# Connectors.net
KiCad netlist of a schematic drawn in Altium Designer
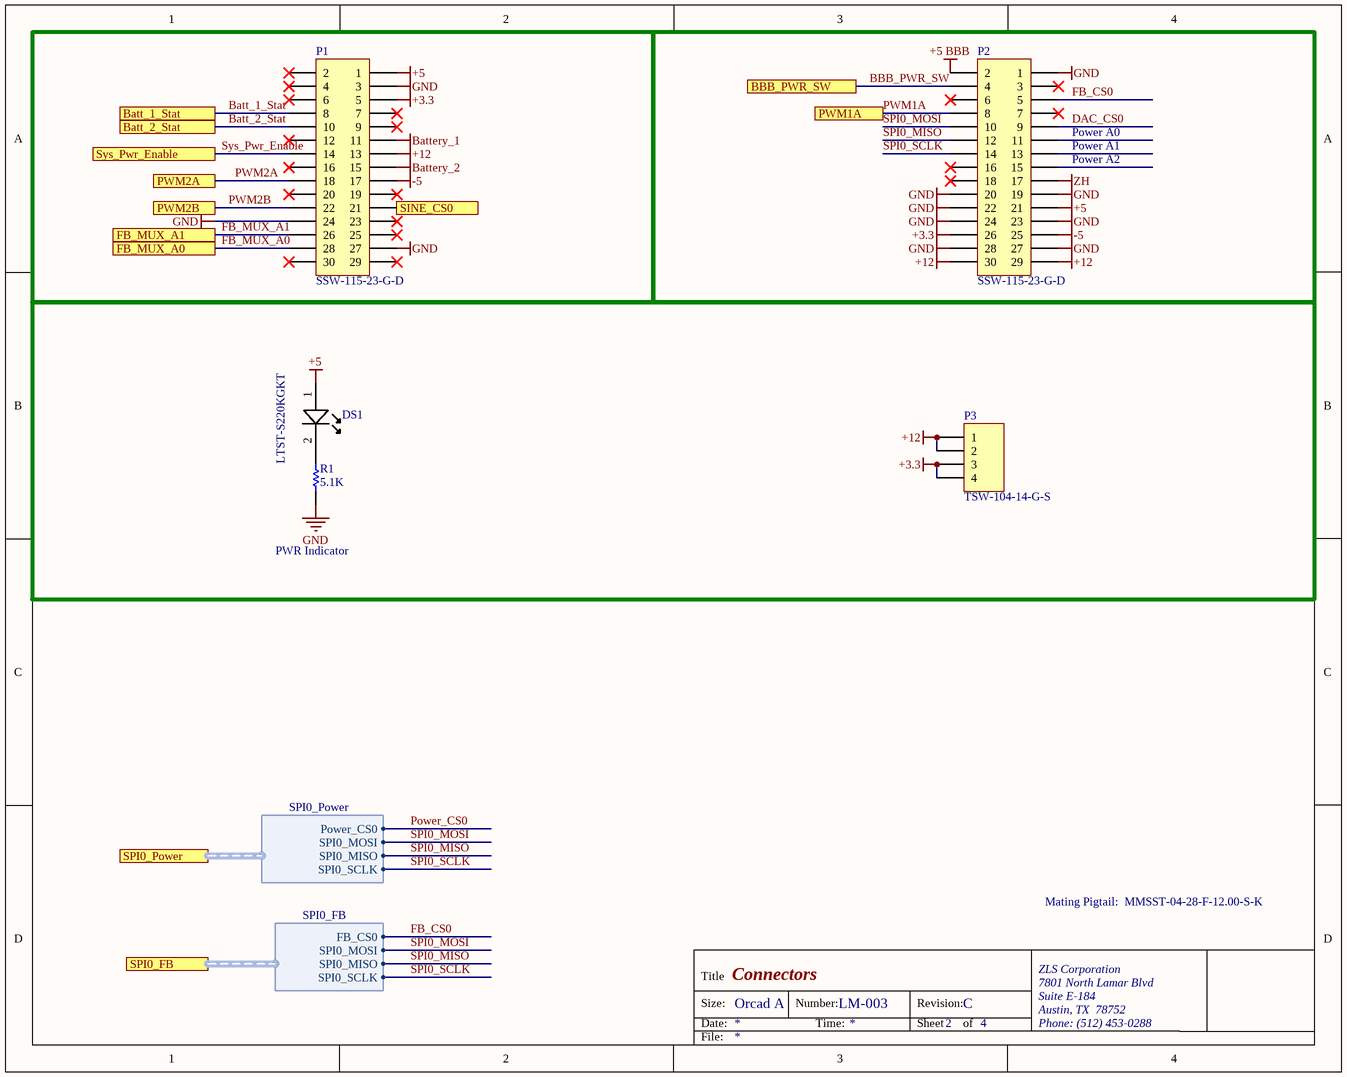
[diagram p0: Connectors.SchDoc]

(export (version "E")
  (design (tool "Eeschema 10.0.6"))
  (components
    (comp (ref "DS1")
      (value "Lite-On LTST-S220KGKT Green LED, 571 nm 2012 (0805) Side View, Rectangle Lens SMD package")
      (footprint "0805C_L")
      (fields
        (field (name "MANUFACTURER") "Vishay / Lite-On")
        (field (name "MANUFACTURER PART NUMBER") "LTST-S220KGKT")
      )
      (libsource (lib "*") (part "LED A/K"))
    )
    (comp (ref "P1")
      (value "SSW-115-23-G-D")
      (footprint "SSW-115-23-G-D")
      (description "Header, 15-Pin, Dual row")
      (fields (field (name "MANUFACTURER") "Samtec Inc."))
      (libsource (lib "Miscellaneous Connectors") (part "Header 15X2"))
    )
    (comp (ref "P2")
      (value "SSW-115-23-G-D")
      (footprint "SSW-115-23-G-D")
      (description "Header, 15-Pin, Dual row")
      (fields (field (name "MANUFACTURER") "Samtec Inc."))
      (libsource (lib "Miscellaneous Connectors") (part "Header 15X2"))
    )
    (comp (ref "P3")
      (value "TSW-104-14-G-S")
      (footprint "HDR1X4")
      (description "Header, 4-Pin")
      (fields (field (name "MANUFACTURER") "Samtec Inc."))
      (libsource (lib "Miscellaneous Connectors") (part "Header 4"))
    )
    (comp (ref "R1")
      (value "5.1K")
      (footprint "RESC0805(2012)_L")
      (description "RES SMD 5.1K OHM 5% 1/8W 0805")
      (fields
        (field (name "MANUFACTURER") "Vishay Dale")
        (field (name "MANUFACTURER PART NUMBER") "CRCW08055K10JNEA")
      )
      (libsource (lib "Altium Content Vault") (part "CMP-1013-00215-1"))
    )
  )
  (nets
    (net (code "3") (name "+3.3") (class "Default")
      (node (ref "P1") (pin "5") (pinfunction "5_5") (pintype "passive"))
      (node (ref "P2") (pin "26") (pinfunction "26_26") (pintype "passive"))
      (node (ref "P3") (pin "3") (pinfunction "3_3") (pintype "passive"))
      (node (ref "P3") (pin "4") (pinfunction "4_4") (pintype "passive"))
    )
    (net (code "4") (name "+5") (class "Default")
      (node (ref "DS1") (pin "1") (pinfunction "A_1") (pintype "passive"))
      (node (ref "P1") (pin "1") (pinfunction "1_1") (pintype "passive"))
      (node (ref "P2") (pin "21") (pinfunction "21_21") (pintype "passive"))
    )
    (net (code "5") (name "+5 BBB") (class "Default")
      (node (ref "P2") (pin "2") (pinfunction "2_2") (pintype "passive"))
    )
    (net (code "6") (name "+12") (class "Default")
      (node (ref "P1") (pin "13") (pinfunction "13_13") (pintype "passive"))
      (node (ref "P2") (pin "29") (pinfunction "29_29") (pintype "passive"))
      (node (ref "P2") (pin "30") (pinfunction "30_30") (pintype "passive"))
      (node (ref "P3") (pin "1") (pinfunction "1_1") (pintype "passive"))
      (node (ref "P3") (pin "2") (pinfunction "2_2") (pintype "passive"))
    )
    (net (code "7") (name "-5") (class "Default")
      (node (ref "P1") (pin "17") (pinfunction "17_17") (pintype "passive"))
      (node (ref "P2") (pin "25") (pinfunction "25_25") (pintype "passive"))
    )
    (net (code "8") (name "/BBB_PWR_SW") (class "Default")
      (node (ref "P2") (pin "4") (pinfunction "4_4") (pintype "passive"))
    )
    (net (code "9") (name "/Batt_1_Stat") (class "Default")
      (node (ref "P1") (pin "8") (pinfunction "8_8") (pintype "passive"))
    )
    (net (code "10") (name "/Batt_2_Stat") (class "Default")
      (node (ref "P1") (pin "10") (pinfunction "10_10") (pintype "passive"))
    )
    (net (code "11") (name "/DAC_CS0") (class "Default")
      (node (ref "P2") (pin "9") (pinfunction "9_9") (pintype "passive"))
    )
    (net (code "12") (name "/FB_CS0") (class "Default")
      (node (ref "P2") (pin "5") (pinfunction "5_5") (pintype "passive"))
    )
    (net (code "13") (name "/FB_MUX_A0") (class "Default")
      (node (ref "P1") (pin "28") (pinfunction "28_28") (pintype "passive"))
    )
    (net (code "14") (name "/FB_MUX_A1") (class "Default")
      (node (ref "P1") (pin "26") (pinfunction "26_26") (pintype "passive"))
    )
    (net (code "15") (name "/PWM1A") (class "Default")
      (node (ref "P2") (pin "8") (pinfunction "8_8") (pintype "passive"))
    )
    (net (code "16") (name "/PWM2A") (class "Default")
      (node (ref "P1") (pin "18") (pinfunction "18_18") (pintype "passive"))
    )
    (net (code "17") (name "/PWM2B") (class "Default")
      (node (ref "P1") (pin "22") (pinfunction "22_22") (pintype "passive"))
    )
    (net (code "19") (name "/SINE_CS0") (class "Default")
      (node (ref "P1") (pin "21") (pinfunction "21_21") (pintype "passive"))
    )
    (net (code "20") (name "/SPI0_MISO") (class "Default")
      (node (ref "P2") (pin "12") (pinfunction "12_12") (pintype "passive"))
    )
    (net (code "21") (name "/SPI0_MOSI") (class "Default")
      (node (ref "P2") (pin "10") (pinfunction "10_10") (pintype "passive"))
    )
    (net (code "22") (name "/SPI0_SCLK") (class "Default")
      (node (ref "P2") (pin "14") (pinfunction "14_14") (pintype "passive"))
    )
    (net (code "23") (name "/Sys_Pwr_Enable") (class "Default")
      (node (ref "P1") (pin "14") (pinfunction "14_14") (pintype "passive"))
    )
    (net (code "26") (name "Battery_1") (class "Default")
      (node (ref "P1") (pin "11") (pinfunction "11_11") (pintype "passive"))
    )
    (net (code "27") (name "Battery_2") (class "Default")
      (node (ref "P1") (pin "15") (pinfunction "15_15") (pintype "passive"))
    )
    (net (code "28") (name "GND") (class "Default")
      (node (ref "P1") (pin "24") (pinfunction "24_24") (pintype "passive"))
      (node (ref "P1") (pin "27") (pinfunction "27_27") (pintype "passive"))
      (node (ref "P1") (pin "3") (pinfunction "3_3") (pintype "passive"))
      (node (ref "P2") (pin "1") (pinfunction "1_1") (pintype "passive"))
      (node (ref "P2") (pin "19") (pinfunction "19_19") (pintype "passive"))
      (node (ref "P2") (pin "20") (pinfunction "20_20") (pintype "passive"))
      (node (ref "P2") (pin "22") (pinfunction "22_22") (pintype "passive"))
      (node (ref "P2") (pin "23") (pinfunction "23_23") (pintype "passive"))
      (node (ref "P2") (pin "24") (pinfunction "24_24") (pintype "passive"))
      (node (ref "P2") (pin "27") (pinfunction "27_27") (pintype "passive"))
      (node (ref "P2") (pin "28") (pinfunction "28_28") (pintype "passive"))
      (node (ref "R1") (pin "2") (pinfunction "2_2") (pintype "passive"))
    )
    (net (code "29") (name "Net-(DS1-K)") (class "Default")
      (node (ref "DS1") (pin "2") (pinfunction "K_2") (pintype "passive"))
      (node (ref "R1") (pin "1") (pinfunction "1_1") (pintype "passive"))
    )
    (net (code "30") (name "ZH") (class "Default")
      (node (ref "P2") (pin "17") (pinfunction "17_17") (pintype "passive"))
    )
    (net (code "31") (name "unconnected-(P1-Pad2)") (class "Default")
      (node (ref "P1") (pin "2") (pinfunction "2_2") (pintype "passive+no_connect"))
    )
    (net (code "32") (name "unconnected-(P1-Pad4)") (class "Default")
      (node (ref "P1") (pin "4") (pinfunction "4_4") (pintype "passive+no_connect"))
    )
    (net (code "33") (name "unconnected-(P1-Pad6)") (class "Default")
      (node (ref "P1") (pin "6") (pinfunction "6_6") (pintype "passive+no_connect"))
    )
    (net (code "34") (name "unconnected-(P1-Pad7)") (class "Default")
      (node (ref "P1") (pin "7") (pinfunction "7_7") (pintype "passive+no_connect"))
    )
    (net (code "35") (name "unconnected-(P1-Pad9)") (class "Default")
      (node (ref "P1") (pin "9") (pinfunction "9_9") (pintype "passive+no_connect"))
    )
    (net (code "36") (name "unconnected-(P1-Pad12)") (class "Default")
      (node (ref "P1") (pin "12") (pinfunction "12_12") (pintype "passive+no_connect"))
    )
    (net (code "37") (name "unconnected-(P1-Pad16)") (class "Default")
      (node (ref "P1") (pin "16") (pinfunction "16_16") (pintype "passive+no_connect"))
    )
    (net (code "38") (name "unconnected-(P1-Pad19)") (class "Default")
      (node (ref "P1") (pin "19") (pinfunction "19_19") (pintype "passive+no_connect"))
    )
    (net (code "39") (name "unconnected-(P1-Pad20)") (class "Default")
      (node (ref "P1") (pin "20") (pinfunction "20_20") (pintype "passive+no_connect"))
    )
    (net (code "40") (name "unconnected-(P1-Pad23)") (class "Default")
      (node (ref "P1") (pin "23") (pinfunction "23_23") (pintype "passive+no_connect"))
    )
    (net (code "41") (name "unconnected-(P1-Pad25)") (class "Default")
      (node (ref "P1") (pin "25") (pinfunction "25_25") (pintype "passive+no_connect"))
    )
    (net (code "42") (name "unconnected-(P1-Pad29)") (class "Default")
      (node (ref "P1") (pin "29") (pinfunction "29_29") (pintype "passive+no_connect"))
    )
    (net (code "43") (name "unconnected-(P1-Pad30)") (class "Default")
      (node (ref "P1") (pin "30") (pinfunction "30_30") (pintype "passive+no_connect"))
    )
    (net (code "44") (name "unconnected-(P2-Pad3)") (class "Default")
      (node (ref "P2") (pin "3") (pinfunction "3_3") (pintype "passive+no_connect"))
    )
    (net (code "45") (name "unconnected-(P2-Pad6)") (class "Default")
      (node (ref "P2") (pin "6") (pinfunction "6_6") (pintype "passive+no_connect"))
    )
    (net (code "46") (name "unconnected-(P2-Pad7)") (class "Default")
      (node (ref "P2") (pin "7") (pinfunction "7_7") (pintype "passive+no_connect"))
    )
    (net (code "47") (name "unconnected-(P2-Pad11)") (class "Default")
      (node (ref "P2") (pin "11") (pinfunction "11_11") (pintype "passive"))
    )
    (net (code "48") (name "unconnected-(P2-Pad13)") (class "Default")
      (node (ref "P2") (pin "13") (pinfunction "13_13") (pintype "passive"))
    )
    (net (code "49") (name "unconnected-(P2-Pad15)") (class "Default")
      (node (ref "P2") (pin "15") (pinfunction "15_15") (pintype "passive"))
    )
    (net (code "50") (name "unconnected-(P2-Pad16)") (class "Default")
      (node (ref "P2") (pin "16") (pinfunction "16_16") (pintype "passive+no_connect"))
    )
    (net (code "51") (name "unconnected-(P2-Pad18)") (class "Default")
      (node (ref "P2") (pin "18") (pinfunction "18_18") (pintype "passive+no_connect"))
    )
  )
)
